# 8RelaySwitch.net
KiCad netlist of a schematic drawn in EAGLE
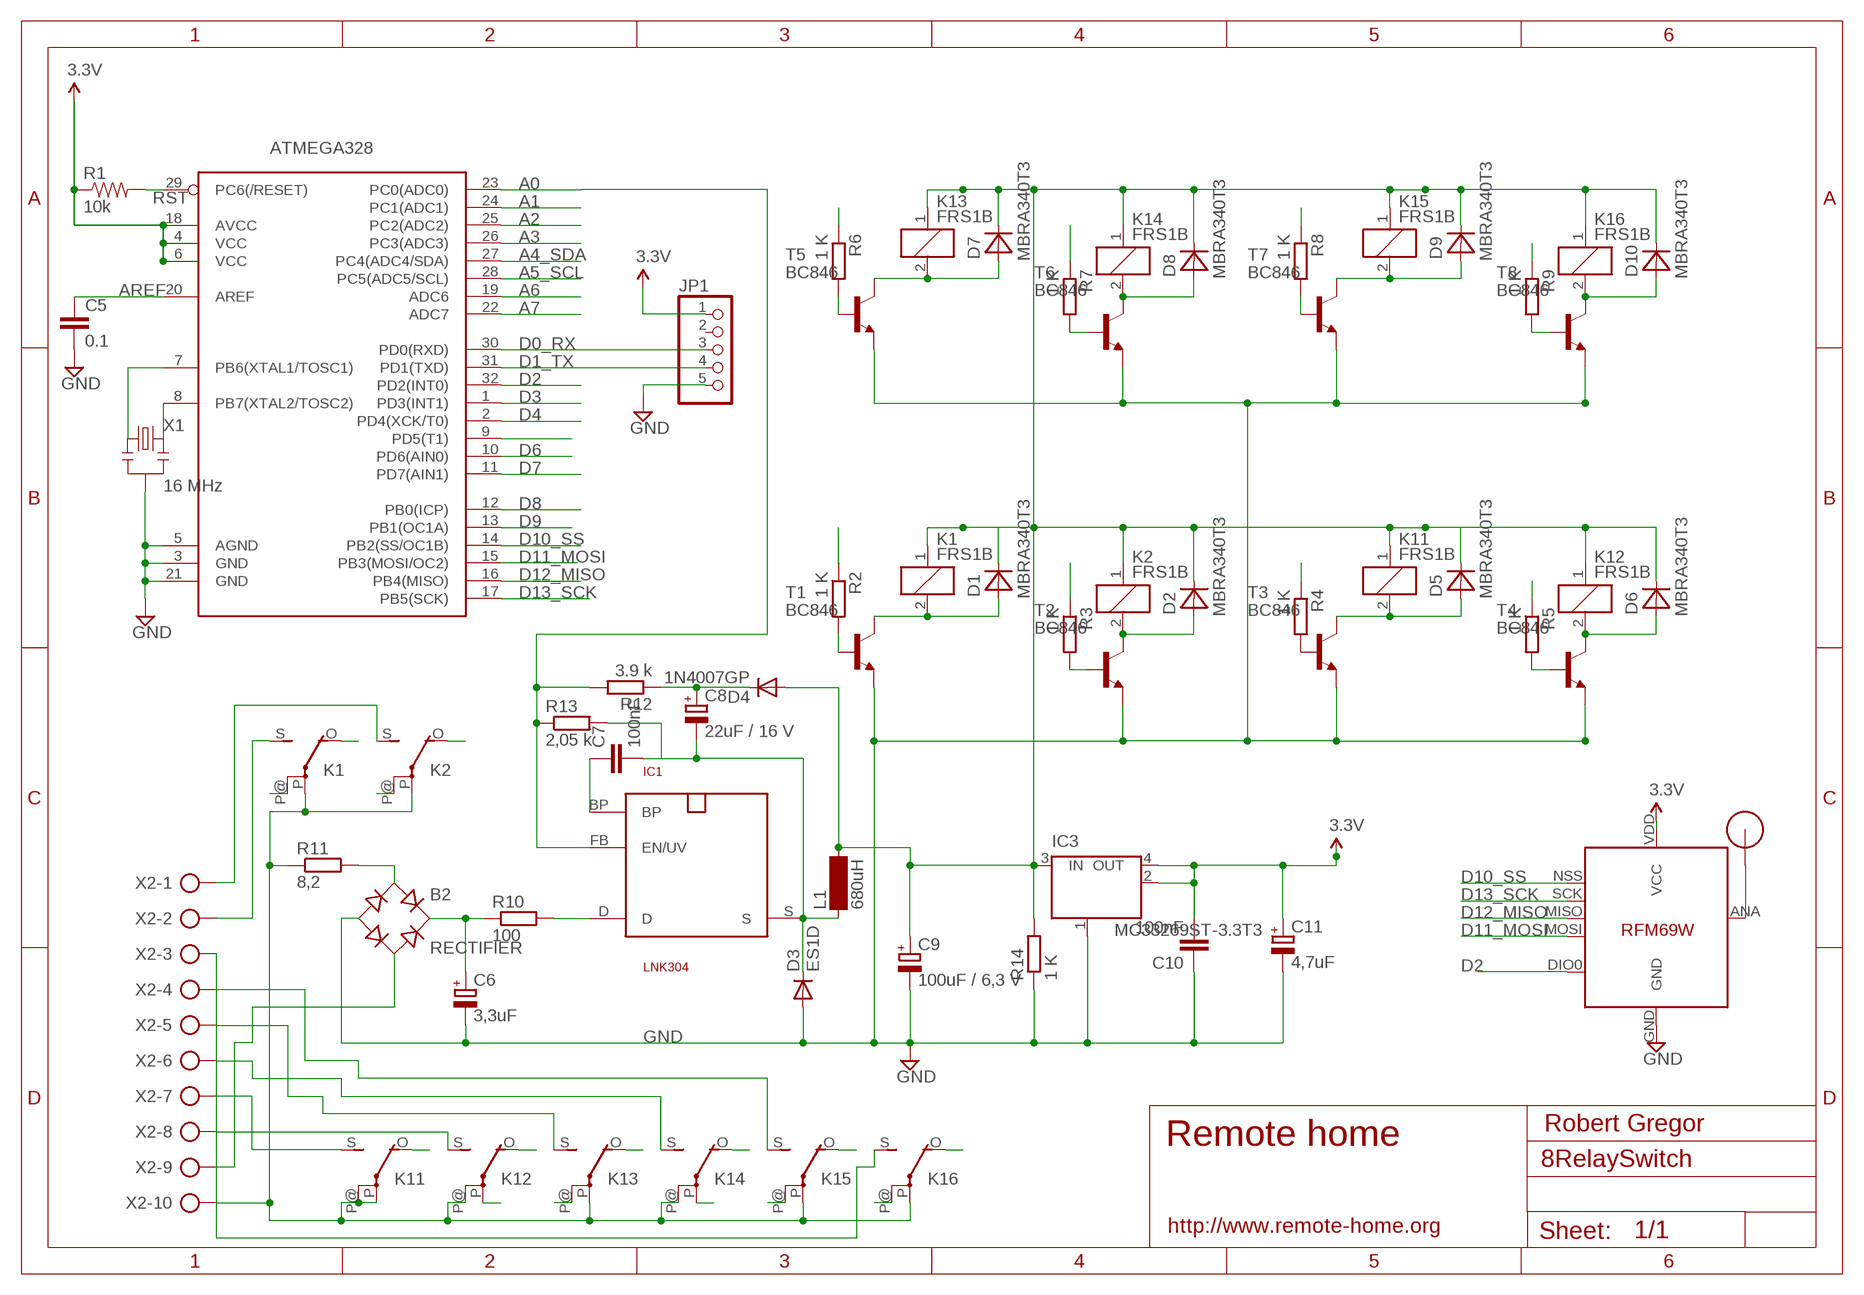
[diagram p0: schematic, sheet 1]

(export (version "E")
  (design (tool "Eeschema 10.0.6"))
  (components
    (comp (ref "ATMEGA328")
      (value "ATMega-328")
      (footprint "eagle-import:TQFP32-08")
      (libsource (lib "eagle-import") (part "ATMEGA168/328TQFP32"))
    )
    (comp (ref "B2")
      (value "RECTIFIER")
      (footprint "eagle-import:TO-269AA")
      (libsource (lib "eagle-import") (part "RECTIFIER-S40"))
    )
    (comp (ref "C5")
      (value "0.1")
      (footprint "eagle-import:0603-CAP")
      (libsource (lib "eagle-import") (part "CAP0603-CAP"))
    )
    (comp (ref "C6")
      (value "3,3uF")
      (footprint "eagle-import:E5-10,5")
      (libsource (lib "eagle-import") (part "CPOL-EUE5-10.5"))
    )
    (comp (ref "C7")
      (value "100nF")
      (footprint "eagle-import:C2012")
      (libsource (lib "eagle-import") (part "C-EUC2012"))
    )
    (comp (ref "C8")
      (value "22uF / 16 V")
      (footprint "eagle-import:SMC_C")
      (libsource (lib "eagle-import") (part "CPOL-EUSMCC"))
    )
    (comp (ref "C9")
      (value "100uF / 6,3 V")
      (footprint "eagle-import:E2,5-5")
      (libsource (lib "eagle-import") (part "CPOL-EUE2.5-5"))
    )
    (comp (ref "C10")
      (value "100nF")
      (footprint "eagle-import:C2012")
      (libsource (lib "eagle-import") (part "C-EUC2012"))
    )
    (comp (ref "C11")
      (value "4,7uF")
      (footprint "eagle-import:SMC_A")
      (libsource (lib "eagle-import") (part "CPOL-EUSMCA"))
    )
    (comp (ref "D1")
      (value "MBRA340T3")
      (footprint "eagle-import:SMA")
      (libsource (lib "eagle-import") (part "MBRA340T3"))
    )
    (comp (ref "D2")
      (value "MBRA340T3")
      (footprint "eagle-import:SMA")
      (libsource (lib "eagle-import") (part "MBRA340T3"))
    )
    (comp (ref "D3")
      (value "ES1D")
      (footprint "eagle-import:DO214AC")
      (libsource (lib "eagle-import") (part "DIODE-DO214AC"))
    )
    (comp (ref "D4")
      (value "1N4007GP")
      (footprint "eagle-import:DO214AA")
      (libsource (lib "eagle-import") (part "DIODE-DO214AA"))
    )
    (comp (ref "D5")
      (value "MBRA340T3")
      (footprint "eagle-import:SMA")
      (libsource (lib "eagle-import") (part "MBRA340T3"))
    )
    (comp (ref "D6")
      (value "MBRA340T3")
      (footprint "eagle-import:SMA")
      (libsource (lib "eagle-import") (part "MBRA340T3"))
    )
    (comp (ref "D7")
      (value "MBRA340T3")
      (footprint "eagle-import:SMA")
      (libsource (lib "eagle-import") (part "MBRA340T3"))
    )
    (comp (ref "D8")
      (value "MBRA340T3")
      (footprint "eagle-import:SMA")
      (libsource (lib "eagle-import") (part "MBRA340T3"))
    )
    (comp (ref "D9")
      (value "MBRA340T3")
      (footprint "eagle-import:SMA")
      (libsource (lib "eagle-import") (part "MBRA340T3"))
    )
    (comp (ref "D10")
      (value "MBRA340T3")
      (footprint "eagle-import:SMA")
      (libsource (lib "eagle-import") (part "MBRA340T3"))
    )
    (comp (ref "IC1")
      (value "LNK304")
      (footprint "eagle-import:SO-8C")
      (libsource (lib "eagle-import") (part "SO-8C"))
    )
    (comp (ref "IC3")
      (value "MC33269ST-3.3T3")
      (footprint "eagle-import:SOT223")
      (libsource (lib "eagle-import") (part "MC33269ST-3.3T3"))
    )
    (comp (ref "JP1")
      (value "PINHD-1X5")
      (footprint "eagle-import:1X05")
      (libsource (lib "eagle-import") (part "PINHD-1X5"))
    )
    (comp (ref "K1")
      (value "FRS1B")
      (footprint "eagle-import:FRS1B")
      (libsource (lib "eagle-import") (part "FRS1B"))
    )
    (comp (ref "K2")
      (value "FRS1B")
      (footprint "eagle-import:FRS1B")
      (libsource (lib "eagle-import") (part "FRS1B"))
    )
    (comp (ref "K11")
      (value "FRS1B")
      (footprint "eagle-import:FRS1B")
      (libsource (lib "eagle-import") (part "FRS1B"))
    )
    (comp (ref "K12")
      (value "FRS1B")
      (footprint "eagle-import:FRS1B")
      (libsource (lib "eagle-import") (part "FRS1B"))
    )
    (comp (ref "K13")
      (value "FRS1B")
      (footprint "eagle-import:FRS1B")
      (libsource (lib "eagle-import") (part "FRS1B"))
    )
    (comp (ref "K14")
      (value "FRS1B")
      (footprint "eagle-import:FRS1B")
      (libsource (lib "eagle-import") (part "FRS1B"))
    )
    (comp (ref "K15")
      (value "FRS1B")
      (footprint "eagle-import:FRS1B")
      (libsource (lib "eagle-import") (part "FRS1B"))
    )
    (comp (ref "K16")
      (value "FRS1B")
      (footprint "eagle-import:FRS1B")
      (libsource (lib "eagle-import") (part "FRS1B"))
    )
    (comp (ref "L1")
      (value "680uH")
      (footprint "eagle-import:BS11")
      (libsource (lib "eagle-import") (part "BS11"))
    )
    (comp (ref "R1")
      (value "10k")
      (footprint "eagle-import:0603-RES")
      (libsource (lib "eagle-import") (part "RESISTOR0603-RES"))
    )
    (comp (ref "R2")
      (value "1 K")
      (footprint "eagle-import:M2012")
      (libsource (lib "eagle-import") (part "R-EU_M2012"))
    )
    (comp (ref "R3")
      (value "1 K")
      (footprint "eagle-import:M2012")
      (libsource (lib "eagle-import") (part "R-EU_M2012"))
    )
    (comp (ref "R4")
      (value "1 K")
      (footprint "eagle-import:M2012")
      (libsource (lib "eagle-import") (part "R-EU_M2012"))
    )
    (comp (ref "R5")
      (value "1 K")
      (footprint "eagle-import:M2012")
      (libsource (lib "eagle-import") (part "R-EU_M2012"))
    )
    (comp (ref "R6")
      (value "1 K")
      (footprint "eagle-import:M2012")
      (libsource (lib "eagle-import") (part "R-EU_M2012"))
    )
    (comp (ref "R7")
      (value "1 K")
      (footprint "eagle-import:M2012")
      (libsource (lib "eagle-import") (part "R-EU_M2012"))
    )
    (comp (ref "R8")
      (value "1 K")
      (footprint "eagle-import:M2012")
      (libsource (lib "eagle-import") (part "R-EU_M2012"))
    )
    (comp (ref "R9")
      (value "1 K")
      (footprint "eagle-import:M2012")
      (libsource (lib "eagle-import") (part "R-EU_M2012"))
    )
    (comp (ref "R10")
      (value "100")
      (footprint "eagle-import:R2512W")
      (libsource (lib "eagle-import") (part "R-EU_R2512W"))
    )
    (comp (ref "R11")
      (value "8,2")
      (footprint "eagle-import:0411_12")
      (libsource (lib "eagle-import") (part "R-EU_0411/12"))
    )
    (comp (ref "R12")
      (value "3.9 k")
      (footprint "eagle-import:M2012")
      (libsource (lib "eagle-import") (part "R-EU_M2012"))
    )
    (comp (ref "R13")
      (value "2,05 k")
      (footprint "eagle-import:M2012")
      (libsource (lib "eagle-import") (part "R-EU_M2012"))
    )
    (comp (ref "R14")
      (value "1 K")
      (footprint "eagle-import:M2012")
      (libsource (lib "eagle-import") (part "R-EU_M2012"))
    )
    (comp (ref "T1")
      (value "BC846")
      (footprint "eagle-import:SOT23")
      (libsource (lib "eagle-import") (part "BC846"))
    )
    (comp (ref "T2")
      (value "BC846")
      (footprint "eagle-import:SOT23")
      (libsource (lib "eagle-import") (part "BC846"))
    )
    (comp (ref "T3")
      (value "BC846")
      (footprint "eagle-import:SOT23")
      (libsource (lib "eagle-import") (part "BC846"))
    )
    (comp (ref "T4")
      (value "BC846")
      (footprint "eagle-import:SOT23")
      (libsource (lib "eagle-import") (part "BC846"))
    )
    (comp (ref "T5")
      (value "BC846")
      (footprint "eagle-import:SOT23")
      (libsource (lib "eagle-import") (part "BC846"))
    )
    (comp (ref "T6")
      (value "BC846")
      (footprint "eagle-import:SOT23")
      (libsource (lib "eagle-import") (part "BC846"))
    )
    (comp (ref "T7")
      (value "BC846")
      (footprint "eagle-import:SOT23")
      (libsource (lib "eagle-import") (part "BC846"))
    )
    (comp (ref "T8")
      (value "BC846")
      (footprint "eagle-import:SOT23")
      (libsource (lib "eagle-import") (part "BC846"))
    )
    (comp (ref "U$1")
      (value "RFM12B_ANTENNA")
      (footprint "eagle-import:RFM12B-ANTENNA")
      (libsource (lib "eagle-import") (part "RFM12B_ANTENNA"))
    )
    (comp (ref "U$5")
      (value "RFM69")
      (footprint "eagle-import:RFM69W-MINPADS")
      (libsource (lib "eagle-import") (part "RFM69"))
    )
    (comp (ref "X1")
      (value "16 MHz")
      (footprint "eagle-import:RESONATOR-SMD")
      (libsource (lib "eagle-import") (part "RESONATORSMD"))
    )
    (comp (ref "X2")
      (value "AK500/10")
      (footprint "eagle-import:AK500_10")
      (libsource (lib "eagle-import") (part "AK500/10"))
    )
  )
  (nets
    (net (code "1") (name "/A0") (class "Default")
      (node (ref "ATMEGA328") (pin "23") (pinfunction "PC0(ADC0)_23") (pintype "bidirectional"))
      (node (ref "IC1") (pin "FB") (pinfunction "EN/UV_FB") (pintype "input"))
      (node (ref "R12") (pin "2") (pinfunction "2_2") (pintype "passive"))
      (node (ref "R13") (pin "1") (pinfunction "1_1") (pintype "passive"))
    )
    (net (code "2") (name "/A1") (class "Default")
      (node (ref "ATMEGA328") (pin "24") (pinfunction "PC1(ADC1)_24") (pintype "bidirectional"))
      (node (ref "R6") (pin "1") (pinfunction "1_1") (pintype "passive"))
    )
    (net (code "3") (name "/A2") (class "Default")
      (node (ref "ATMEGA328") (pin "25") (pinfunction "PC2(ADC2)_25") (pintype "bidirectional"))
    )
    (net (code "4") (name "/A3") (class "Default")
      (node (ref "ATMEGA328") (pin "26") (pinfunction "PC3(ADC3)_26") (pintype "bidirectional"))
    )
    (net (code "5") (name "/A4_SDA") (class "Default")
      (node (ref "ATMEGA328") (pin "27") (pinfunction "PC4(ADC4/SDA)_27") (pintype "bidirectional"))
    )
    (net (code "6") (name "/A5_SCL") (class "Default")
      (node (ref "ATMEGA328") (pin "28") (pinfunction "PC5(ADC5/SCL)_28") (pintype "bidirectional"))
    )
    (net (code "7") (name "/A6") (class "Default")
      (node (ref "ATMEGA328") (pin "19") (pinfunction "ADC6_19") (pintype "bidirectional"))
    )
    (net (code "8") (name "/A7") (class "Default")
      (node (ref "ATMEGA328") (pin "22") (pinfunction "ADC7_22") (pintype "bidirectional"))
    )
    (net (code "9") (name "/AREF") (class "Default")
      (node (ref "ATMEGA328") (pin "20") (pinfunction "AREF_20") (pintype "bidirectional"))
      (node (ref "C5") (pin "1") (pinfunction "1_1") (pintype "passive"))
    )
    (net (code "10") (name "/D0_RX") (class "Default")
      (node (ref "ATMEGA328") (pin "30") (pinfunction "PD0(RXD)_30") (pintype "bidirectional"))
      (node (ref "JP1") (pin "3") (pinfunction "3_3") (pintype "passive"))
    )
    (net (code "11") (name "/D1_TX") (class "Default")
      (node (ref "ATMEGA328") (pin "31") (pinfunction "PD1(TXD)_31") (pintype "bidirectional"))
      (node (ref "JP1") (pin "4") (pinfunction "4_4") (pintype "passive"))
    )
    (net (code "12") (name "/D2") (class "Default")
      (node (ref "ATMEGA328") (pin "32") (pinfunction "PD2(INT0)_32") (pintype "bidirectional"))
      (node (ref "U$5") (pin "DIO0") (pinfunction "DIO0_DIO0") (pintype "open_collector"))
    )
    (net (code "13") (name "/D3") (class "Default")
      (node (ref "ATMEGA328") (pin "1") (pinfunction "PD3(INT1)_1") (pintype "bidirectional"))
      (node (ref "R7") (pin "1") (pinfunction "1_1") (pintype "passive"))
    )
    (net (code "14") (name "/D4") (class "Default")
      (node (ref "ATMEGA328") (pin "2") (pinfunction "PD4(XCK/T0)_2") (pintype "bidirectional"))
      (node (ref "R8") (pin "1") (pinfunction "1_1") (pintype "passive"))
    )
    (net (code "15") (name "/D5") (class "Default")
      (node (ref "ATMEGA328") (pin "9") (pinfunction "PD5(T1)_9") (pintype "bidirectional"))
      (node (ref "R2") (pin "1") (pinfunction "1_1") (pintype "passive"))
    )
    (net (code "16") (name "/D6") (class "Default")
      (node (ref "ATMEGA328") (pin "10") (pinfunction "PD6(AIN0)_10") (pintype "bidirectional"))
      (node (ref "R3") (pin "1") (pinfunction "1_1") (pintype "passive"))
    )
    (net (code "17") (name "/D7") (class "Default")
      (node (ref "ATMEGA328") (pin "11") (pinfunction "PD7(AIN1)_11") (pintype "bidirectional"))
      (node (ref "R4") (pin "1") (pinfunction "1_1") (pintype "passive"))
    )
    (net (code "18") (name "/D8") (class "Default")
      (node (ref "ATMEGA328") (pin "12") (pinfunction "PB0(ICP)_12") (pintype "bidirectional"))
      (node (ref "R5") (pin "1") (pinfunction "1_1") (pintype "passive"))
    )
    (net (code "19") (name "/D9") (class "Default")
      (node (ref "ATMEGA328") (pin "13") (pinfunction "PB1(OC1A)_13") (pintype "bidirectional"))
      (node (ref "R9") (pin "1") (pinfunction "1_1") (pintype "passive"))
    )
    (net (code "20") (name "/D10_SS") (class "Default")
      (node (ref "ATMEGA328") (pin "14") (pinfunction "PB2(SS/OC1B)_14") (pintype "bidirectional"))
      (node (ref "U$5") (pin "NSS") (pinfunction "SEL_NSS") (pintype "input"))
    )
    (net (code "21") (name "/D11_MOSI") (class "Default")
      (node (ref "ATMEGA328") (pin "15") (pinfunction "PB3(MOSI/OC2)_15") (pintype "bidirectional"))
      (node (ref "U$5") (pin "MOSI") (pinfunction "MOSI_MOSI") (pintype "output"))
    )
    (net (code "22") (name "/D12_MISO") (class "Default")
      (node (ref "ATMEGA328") (pin "16") (pinfunction "PB4(MISO)_16") (pintype "bidirectional"))
      (node (ref "U$5") (pin "MISO") (pinfunction "MISO_MISO") (pintype "input"))
    )
    (net (code "23") (name "/D13_SCK") (class "Default")
      (node (ref "ATMEGA328") (pin "17") (pinfunction "PB5(SCK)_17") (pintype "bidirectional"))
      (node (ref "U$5") (pin "SCK") (pinfunction "SCK_SCK") (pintype "input"))
    )
    (net (code "24") (name "/RST") (class "Default")
      (node (ref "ATMEGA328") (pin "29") (pinfunction "PC6(/RESET)_29") (pintype "bidirectional"))
      (node (ref "R1") (pin "2") (pinfunction "2_2") (pintype "passive"))
    )
    (net (code "25") (name "3.3V") (class "Default")
      (node (ref "ATMEGA328") (pin "18") (pinfunction "AVCC_18") (pintype "bidirectional"))
      (node (ref "ATMEGA328") (pin "4") (pinfunction "VCC_4") (pintype "bidirectional"))
      (node (ref "ATMEGA328") (pin "6") (pinfunction "VCC_6") (pintype "bidirectional"))
      (node (ref "C10") (pin "2") (pinfunction "2_2") (pintype "passive"))
      (node (ref "C11") (pin "+") (pinfunction "+_+") (pintype "passive"))
      (node (ref "IC3") (pin "2") (pinfunction "OUT_2") (pintype "passive"))
      (node (ref "IC3") (pin "4") (pinfunction "OUT_4") (pintype "passive"))
      (node (ref "JP1") (pin "1") (pinfunction "1_1") (pintype "passive"))
      (node (ref "R1") (pin "1") (pinfunction "1_1") (pintype "passive"))
      (node (ref "U$5") (pin "VDD") (pinfunction "VCC_VDD") (pintype "power_in"))
    )
    (net (code "26") (name "GND") (class "Default")
      (node (ref "ATMEGA328") (pin "21") (pinfunction "GND_21") (pintype "bidirectional"))
      (node (ref "ATMEGA328") (pin "3") (pinfunction "GND_3") (pintype "bidirectional"))
      (node (ref "ATMEGA328") (pin "5") (pinfunction "AGND_5") (pintype "bidirectional"))
      (node (ref "B2") (pin "-") (pinfunction "-_-") (pintype "passive"))
      (node (ref "C10") (pin "1") (pinfunction "1_1") (pintype "passive"))
      (node (ref "C11") (pin "-") (pinfunction "-_-") (pintype "passive"))
      (node (ref "C5") (pin "2") (pinfunction "2_2") (pintype "passive"))
      (node (ref "C6") (pin "-") (pinfunction "-_-") (pintype "passive"))
      (node (ref "C9") (pin "-") (pinfunction "-_-") (pintype "passive"))
      (node (ref "D3") (pin "A") (pinfunction "A_A") (pintype "passive"))
      (node (ref "IC3") (pin "1") (pinfunction "GND/ADJ_1") (pintype "input"))
      (node (ref "JP1") (pin "5") (pinfunction "5_5") (pintype "passive"))
      (node (ref "R14") (pin "1") (pinfunction "1_1") (pintype "passive"))
      (node (ref "T1") (pin "2") (pinfunction "E_2") (pintype "passive"))
      (node (ref "T2") (pin "2") (pinfunction "E_2") (pintype "passive"))
      (node (ref "T3") (pin "2") (pinfunction "E_2") (pintype "passive"))
      (node (ref "T4") (pin "2") (pinfunction "E_2") (pintype "passive"))
      (node (ref "T5") (pin "2") (pinfunction "E_2") (pintype "passive"))
      (node (ref "T6") (pin "2") (pinfunction "E_2") (pintype "passive"))
      (node (ref "T7") (pin "2") (pinfunction "E_2") (pintype "passive"))
      (node (ref "T8") (pin "2") (pinfunction "E_2") (pintype "passive"))
      (node (ref "U$5") (pin "GND") (pinfunction "GND_GND") (pintype "power_in"))
      (node (ref "X1") (pin "2") (pinfunction "2_2") (pintype "passive"))
    )
    (net (code "27") (name "Net-(ATMEGA328-PB6(XTAL1{slash}TOSC1))") (class "Default")
      (node (ref "ATMEGA328") (pin "7") (pinfunction "PB6(XTAL1/TOSC1)_7") (pintype "bidirectional"))
      (node (ref "X1") (pin "1") (pinfunction "1_1") (pintype "passive"))
    )
    (net (code "28") (name "Net-(ATMEGA328-PB7(XTAL2{slash}TOSC2))") (class "Default")
      (node (ref "ATMEGA328") (pin "8") (pinfunction "PB7(XTAL2/TOSC2)_8") (pintype "bidirectional"))
      (node (ref "X1") (pin "3") (pinfunction "3_3") (pintype "passive"))
    )
    (net (code "29") (name "Net-(B2-Pad+)") (class "Default")
      (node (ref "B2") (pin "+") (pinfunction "+_+") (pintype "passive"))
      (node (ref "C6") (pin "+") (pinfunction "+_+") (pintype "passive"))
      (node (ref "R10") (pin "1") (pinfunction "1_1") (pintype "passive"))
    )
    (net (code "30") (name "Net-(B2-PadAC1)") (class "Default")
      (node (ref "B2") (pin "AC1") (pinfunction "AC1_AC1") (pintype "passive"))
      (node (ref "R11") (pin "2") (pinfunction "2_2") (pintype "passive"))
    )
    (net (code "31") (name "Net-(C7-Pad1)") (class "Default")
      (node (ref "C7") (pin "1") (pinfunction "1_1") (pintype "passive"))
      (node (ref "IC1") (pin "BP") (pinfunction "BP_BP") (pintype "passive"))
    )
    (net (code "32") (name "Net-(C7-Pad2)") (class "Default")
      (node (ref "C7") (pin "2") (pinfunction "2_2") (pintype "passive"))
      (node (ref "C8") (pin "-") (pinfunction "-_-") (pintype "passive"))
      (node (ref "D3") (pin "C") (pinfunction "C_C") (pintype "passive"))
      (node (ref "IC1") (pin "S") (pinfunction "S_S") (pintype "power_in"))
      (node (ref "L1") (pin "1") (pinfunction "1_1") (pintype "passive"))
      (node (ref "R13") (pin "2") (pinfunction "2_2") (pintype "passive"))
    )
    (net (code "33") (name "Net-(C8-Pad+)") (class "Default")
      (node (ref "C8") (pin "+") (pinfunction "+_+") (pintype "passive"))
      (node (ref "D4") (pin "C") (pinfunction "C_C") (pintype "passive"))
      (node (ref "R12") (pin "1") (pinfunction "1_1") (pintype "passive"))
    )
    (net (code "34") (name "Net-(IC1-PadD)") (class "Default")
      (node (ref "IC1") (pin "D") (pinfunction "D_D") (pintype "open_collector"))
      (node (ref "R10") (pin "2") (pinfunction "2_2") (pintype "passive"))
    )
    (net (code "35") (name "Net-(IC3-IN)") (class "Default")
      (node (ref "C9") (pin "+") (pinfunction "+_+") (pintype "passive"))
      (node (ref "D1") (pin "C") (pinfunction "C_C") (pintype "passive"))
      (node (ref "D10") (pin "C") (pinfunction "C_C") (pintype "passive"))
      (node (ref "D2") (pin "C") (pinfunction "C_C") (pintype "passive"))
      (node (ref "D4") (pin "A") (pinfunction "A_A") (pintype "passive"))
      (node (ref "D5") (pin "C") (pinfunction "C_C") (pintype "passive"))
      (node (ref "D6") (pin "C") (pinfunction "C_C") (pintype "passive"))
      (node (ref "D7") (pin "C") (pinfunction "C_C") (pintype "passive"))
      (node (ref "D8") (pin "C") (pinfunction "C_C") (pintype "passive"))
      (node (ref "D9") (pin "C") (pinfunction "C_C") (pintype "passive"))
      (node (ref "IC3") (pin "3") (pinfunction "IN_3") (pintype "input"))
      (node (ref "K1") (pin "1") (pinfunction "1_1") (pintype "passive"))
      (node (ref "K11") (pin "1") (pinfunction "1_1") (pintype "passive"))
      (node (ref "K12") (pin "1") (pinfunction "1_1") (pintype "passive"))
      (node (ref "K13") (pin "1") (pinfunction "1_1") (pintype "passive"))
      (node (ref "K14") (pin "1") (pinfunction "1_1") (pintype "passive"))
      (node (ref "K15") (pin "1") (pinfunction "1_1") (pintype "passive"))
      (node (ref "K16") (pin "1") (pinfunction "1_1") (pintype "passive"))
      (node (ref "K2") (pin "1") (pinfunction "1_1") (pintype "passive"))
      (node (ref "L1") (pin "2") (pinfunction "2_2") (pintype "passive"))
      (node (ref "R14") (pin "2") (pinfunction "2_2") (pintype "passive"))
    )
    (net (code "36") (name "Net-(T1-B)") (class "Default")
      (node (ref "R2") (pin "2") (pinfunction "2_2") (pintype "passive"))
      (node (ref "T1") (pin "1") (pinfunction "B_1") (pintype "passive"))
    )
    (net (code "37") (name "Net-(T1-C)") (class "Default")
      (node (ref "D1") (pin "A") (pinfunction "A_A") (pintype "passive"))
      (node (ref "K1") (pin "2") (pinfunction "2_2") (pintype "passive"))
      (node (ref "T1") (pin "3") (pinfunction "C_3") (pintype "passive"))
    )
    (net (code "38") (name "Net-(T2-B)") (class "Default")
      (node (ref "R3") (pin "2") (pinfunction "2_2") (pintype "passive"))
      (node (ref "T2") (pin "1") (pinfunction "B_1") (pintype "passive"))
    )
    (net (code "39") (name "Net-(T2-C)") (class "Default")
      (node (ref "D2") (pin "A") (pinfunction "A_A") (pintype "passive"))
      (node (ref "K2") (pin "2") (pinfunction "2_2") (pintype "passive"))
      (node (ref "T2") (pin "3") (pinfunction "C_3") (pintype "passive"))
    )
    (net (code "40") (name "Net-(T3-B)") (class "Default")
      (node (ref "R4") (pin "2") (pinfunction "2_2") (pintype "passive"))
      (node (ref "T3") (pin "1") (pinfunction "B_1") (pintype "passive"))
    )
    (net (code "41") (name "Net-(T3-C)") (class "Default")
      (node (ref "D5") (pin "A") (pinfunction "A_A") (pintype "passive"))
      (node (ref "K11") (pin "2") (pinfunction "2_2") (pintype "passive"))
      (node (ref "T3") (pin "3") (pinfunction "C_3") (pintype "passive"))
    )
    (net (code "42") (name "Net-(T4-B)") (class "Default")
      (node (ref "R5") (pin "2") (pinfunction "2_2") (pintype "passive"))
      (node (ref "T4") (pin "1") (pinfunction "B_1") (pintype "passive"))
    )
    (net (code "43") (name "Net-(T4-C)") (class "Default")
      (node (ref "D6") (pin "A") (pinfunction "A_A") (pintype "passive"))
      (node (ref "K12") (pin "2") (pinfunction "2_2") (pintype "passive"))
      (node (ref "T4") (pin "3") (pinfunction "C_3") (pintype "passive"))
    )
    (net (code "44") (name "Net-(T5-B)") (class "Default")
      (node (ref "R6") (pin "2") (pinfunction "2_2") (pintype "passive"))
      (node (ref "T5") (pin "1") (pinfunction "B_1") (pintype "passive"))
    )
    (net (code "45") (name "Net-(T5-C)") (class "Default")
      (node (ref "D7") (pin "A") (pinfunction "A_A") (pintype "passive"))
      (node (ref "K13") (pin "2") (pinfunction "2_2") (pintype "passive"))
      (node (ref "T5") (pin "3") (pinfunction "C_3") (pintype "passive"))
    )
    (net (code "46") (name "Net-(T6-B)") (class "Default")
      (node (ref "R7") (pin "2") (pinfunction "2_2") (pintype "passive"))
      (node (ref "T6") (pin "1") (pinfunction "B_1") (pintype "passive"))
    )
    (net (code "47") (name "Net-(T6-C)") (class "Default")
      (node (ref "D8") (pin "A") (pinfunction "A_A") (pintype "passive"))
      (node (ref "K14") (pin "2") (pinfunction "2_2") (pintype "passive"))
      (node (ref "T6") (pin "3") (pinfunction "C_3") (pintype "passive"))
    )
    (net (code "48") (name "Net-(T7-B)") (class "Default")
      (node (ref "R8") (pin "2") (pinfunction "2_2") (pintype "passive"))
      (node (ref "T7") (pin "1") (pinfunction "B_1") (pintype "passive"))
    )
    (net (code "49") (name "Net-(T7-C)") (class "Default")
      (node (ref "D9") (pin "A") (pinfunction "A_A") (pintype "passive"))
      (node (ref "K15") (pin "2") (pinfunction "2_2") (pintype "passive"))
      (node (ref "T7") (pin "3") (pinfunction "C_3") (pintype "passive"))
    )
    (net (code "50") (name "Net-(T8-B)") (class "Default")
      (node (ref "R9") (pin "2") (pinfunction "2_2") (pintype "passive"))
      (node (ref "T8") (pin "1") (pinfunction "B_1") (pintype "passive"))
    )
    (net (code "51") (name "Net-(T8-C)") (class "Default")
      (node (ref "D10") (pin "A") (pinfunction "A_A") (pintype "passive"))
      (node (ref "K16") (pin "2") (pinfunction "2_2") (pintype "passive"))
      (node (ref "T8") (pin "3") (pinfunction "C_3") (pintype "passive"))
    )
    (net (code "52") (name "Net-(U$1-1)") (class "Default")
      (node (ref "U$1") (pin "P$1") (pinfunction "1_P$1") (pintype "bidirectional"))
      (node (ref "U$5") (pin "ANA") (pinfunction "ANT_ANA") (pintype "passive"))
    )
    (net (code "53") (name "Net-(X2A-KL)") (class "Default")
      (node (ref "K2") (pin "S") (pinfunction "S_S") (pintype "passive"))
      (node (ref "X2") (pin "1") (pinfunction "KL_1") (pintype "passive"))
    )
    (net (code "54") (name "Net-(X2B-KL)") (class "Default")
      (node (ref "K1") (pin "P") (pinfunction "P_P") (pintype "passive"))
      (node (ref "K11") (pin "P") (pinfunction "P_P") (pintype "passive"))
      (node (ref "K11") (pin "P@") (pinfunction "P_P@") (pintype "passive"))
      (node (ref "K12") (pin "P@") (pinfunction "P_P@") (pintype "passive"))
      (node (ref "K13") (pin "P") (pinfunction "P_P") (pintype "passive"))
      (node (ref "K14") (pin "P@") (pinfunction "P_P@") (pintype "passive"))
      (node (ref "K15") (pin "P") (pinfunction "P_P") (pintype "passive"))
      (node (ref "K16") (pin "P") (pinfunction "P_P") (pintype "passive"))
      (node (ref "K2") (pin "P") (pinfunction "P_P") (pintype "passive"))
      (node (ref "R11") (pin "1") (pinfunction "1_1") (pintype "passive"))
      (node (ref "X2") (pin "10") (pinfunction "KL_10") (pintype "passive"))
    )
    (net (code "55") (name "Net-(X2C-KL)") (class "Default")
      (node (ref "K1") (pin "S") (pinfunction "S_S") (pintype "passive"))
      (node (ref "X2") (pin "2") (pinfunction "KL_2") (pintype "passive"))
    )
    (net (code "56") (name "Net-(X2D-KL)") (class "Default")
      (node (ref "K16") (pin "S") (pinfunction "S_S") (pintype "passive"))
      (node (ref "X2") (pin "3") (pinfunction "KL_3") (pintype "passive"))
    )
    (net (code "57") (name "Net-(X2E-KL)") (class "Default")
      (node (ref "K15") (pin "S") (pinfunction "S_S") (pintype "passive"))
      (node (ref "X2") (pin "4") (pinfunction "KL_4") (pintype "passive"))
    )
    (net (code "58") (name "Net-(X2F-KL)") (class "Default")
      (node (ref "K13") (pin "S") (pinfunction "S_S") (pintype "passive"))
      (node (ref "X2") (pin "5") (pinfunction "KL_5") (pintype "passive"))
    )
    (net (code "59") (name "Net-(X2G-KL)") (class "Default")
      (node (ref "K14") (pin "S") (pinfunction "S_S") (pintype "passive"))
      (node (ref "X2") (pin "6") (pinfunction "KL_6") (pintype "passive"))
    )
    (net (code "60") (name "Net-(X2H-KL)") (class "Default")
      (node (ref "K11") (pin "S") (pinfunction "S_S") (pintype "passive"))
      (node (ref "X2") (pin "7") (pinfunction "KL_7") (pintype "passive"))
    )
    (net (code "61") (name "Net-(X2I-KL)") (class "Default")
      (node (ref "K12") (pin "S") (pinfunction "S_S") (pintype "passive"))
      (node (ref "X2") (pin "8") (pinfunction "KL_8") (pintype "passive"))
    )
    (net (code "62") (name "Net-(X2J-KL)") (class "Default")
      (node (ref "B2") (pin "AC2") (pinfunction "AC2_AC2") (pintype "passive"))
      (node (ref "X2") (pin "9") (pinfunction "KL_9") (pintype "passive"))
    )
    (net (code "63") (name "unconnected-(JP1-Pad2)") (class "Default")
      (node (ref "JP1") (pin "2") (pinfunction "2_2") (pintype "passive"))
    )
    (net (code "64") (name "unconnected-(K1-PadO)") (class "Default")
      (node (ref "K1") (pin "O") (pinfunction "O_O") (pintype "passive"))
    )
    (net (code "65") (name "unconnected-(K1B-P-PadP@)") (class "Default")
      (node (ref "K1") (pin "P@") (pinfunction "P_P@") (pintype "passive"))
    )
    (net (code "66") (name "unconnected-(K2-PadO)") (class "Default")
      (node (ref "K2") (pin "O") (pinfunction "O_O") (pintype "passive"))
    )
    (net (code "67") (name "unconnected-(K2B-P-PadP@)") (class "Default")
      (node (ref "K2") (pin "P@") (pinfunction "P_P@") (pintype "passive"))
    )
    (net (code "68") (name "unconnected-(K11-PadO)") (class "Default")
      (node (ref "K11") (pin "O") (pinfunction "O_O") (pintype "passive"))
    )
    (net (code "69") (name "unconnected-(K12-PadO)") (class "Default")
      (node (ref "K12") (pin "O") (pinfunction "O_O") (pintype "passive"))
    )
    (net (code "70") (name "unconnected-(K12-PadP)") (class "Default")
      (node (ref "K12") (pin "P") (pinfunction "P_P") (pintype "passive"))
    )
    (net (code "71") (name "unconnected-(K13-PadO)") (class "Default")
      (node (ref "K13") (pin "O") (pinfunction "O_O") (pintype "passive"))
    )
    (net (code "72") (name "unconnected-(K13B-P-PadP@)") (class "Default")
      (node (ref "K13") (pin "P@") (pinfunction "P_P@") (pintype "passive"))
    )
    (net (code "73") (name "unconnected-(K14-PadO)") (class "Default")
      (node (ref "K14") (pin "O") (pinfunction "O_O") (pintype "passive"))
    )
    (net (code "74") (name "unconnected-(K14-PadP)") (class "Default")
      (node (ref "K14") (pin "P") (pinfunction "P_P") (pintype "passive"))
    )
    (net (code "75") (name "unconnected-(K15-PadO)") (class "Default")
      (node (ref "K15") (pin "O") (pinfunction "O_O") (pintype "passive"))
    )
    (net (code "76") (name "unconnected-(K15B-P-PadP@)") (class "Default")
      (node (ref "K15") (pin "P@") (pinfunction "P_P@") (pintype "passive"))
    )
    (net (code "77") (name "unconnected-(K16-PadO)") (class "Default")
      (node (ref "K16") (pin "O") (pinfunction "O_O") (pintype "passive"))
    )
    (net (code "78") (name "unconnected-(K16B-P-PadP@)") (class "Default")
      (node (ref "K16") (pin "P@") (pinfunction "P_P@") (pintype "passive"))
    )
  )
)
